# MC1.net
KiCad netlist of a schematic drawn in Altium Designer
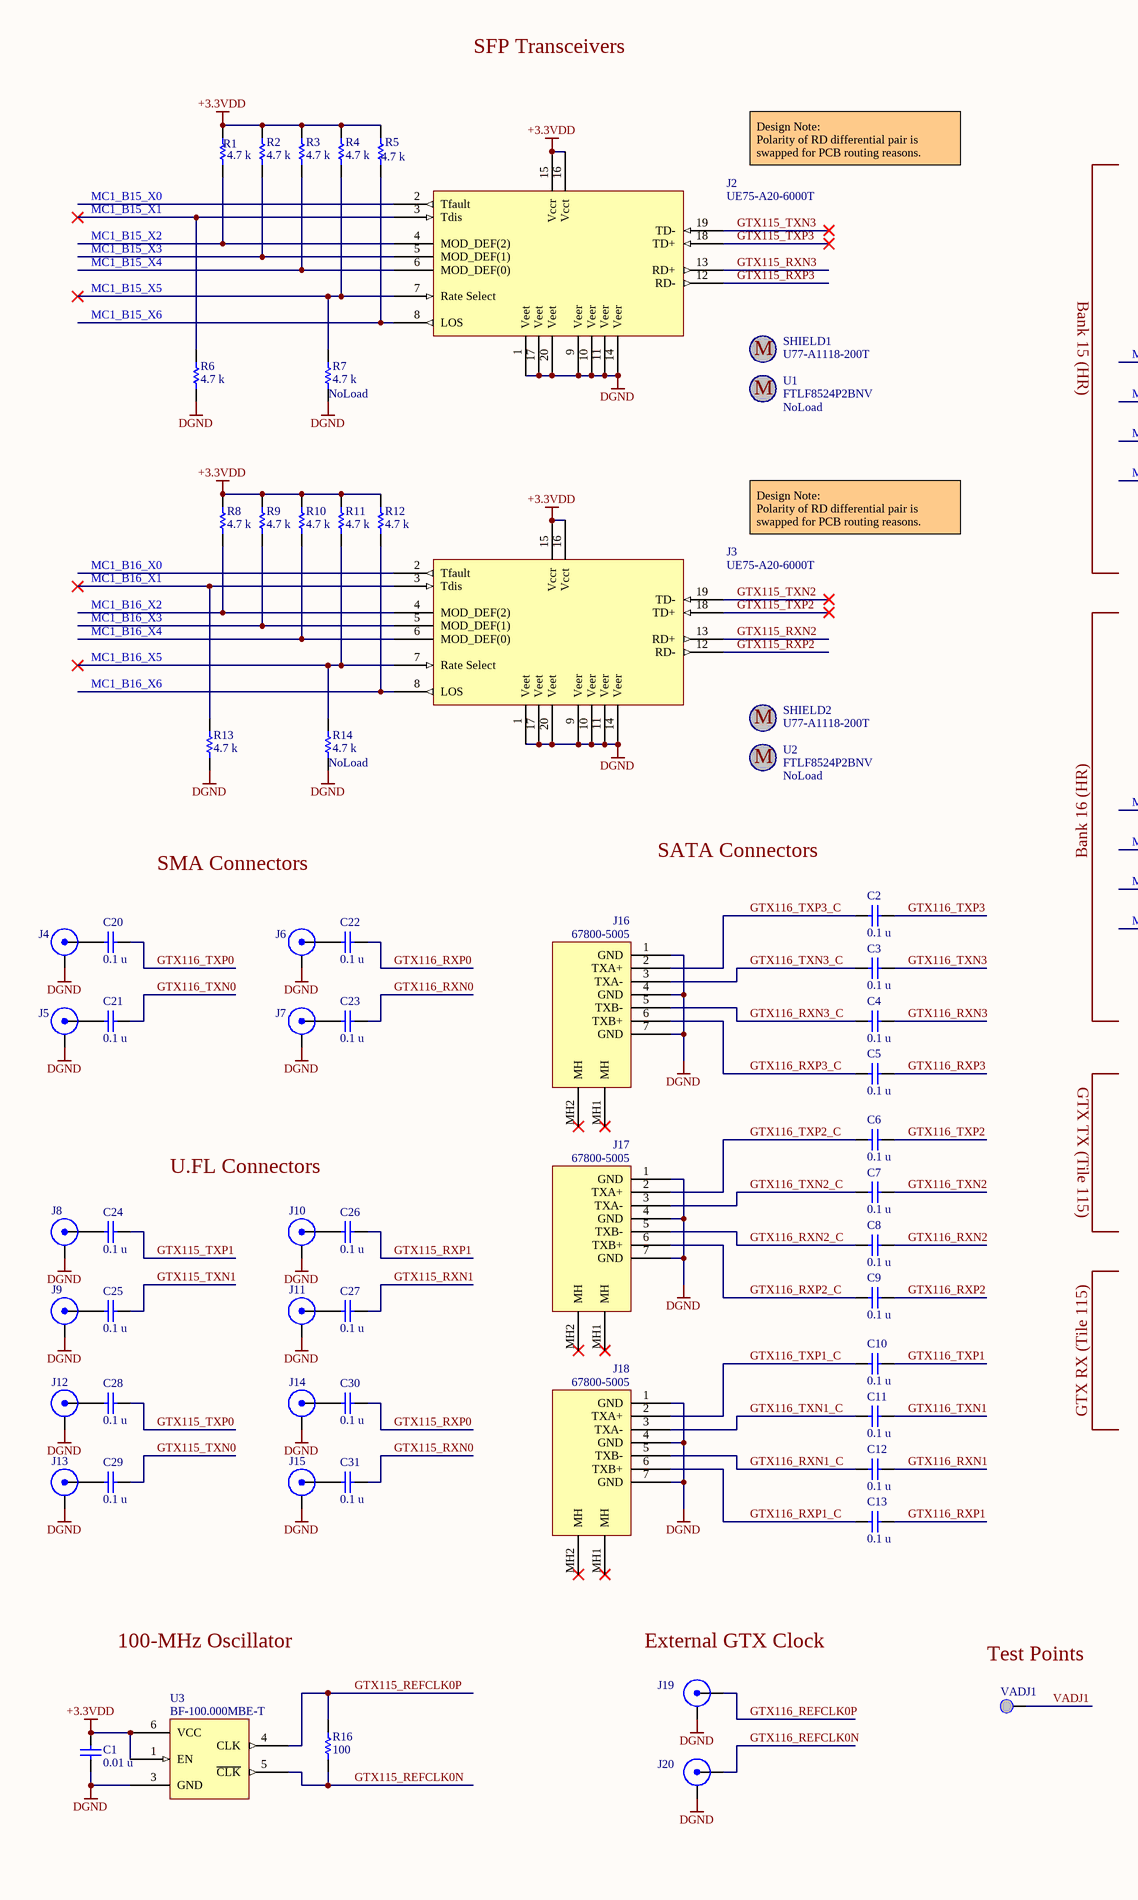
[diagram p0: MC1.SchDoc, left]
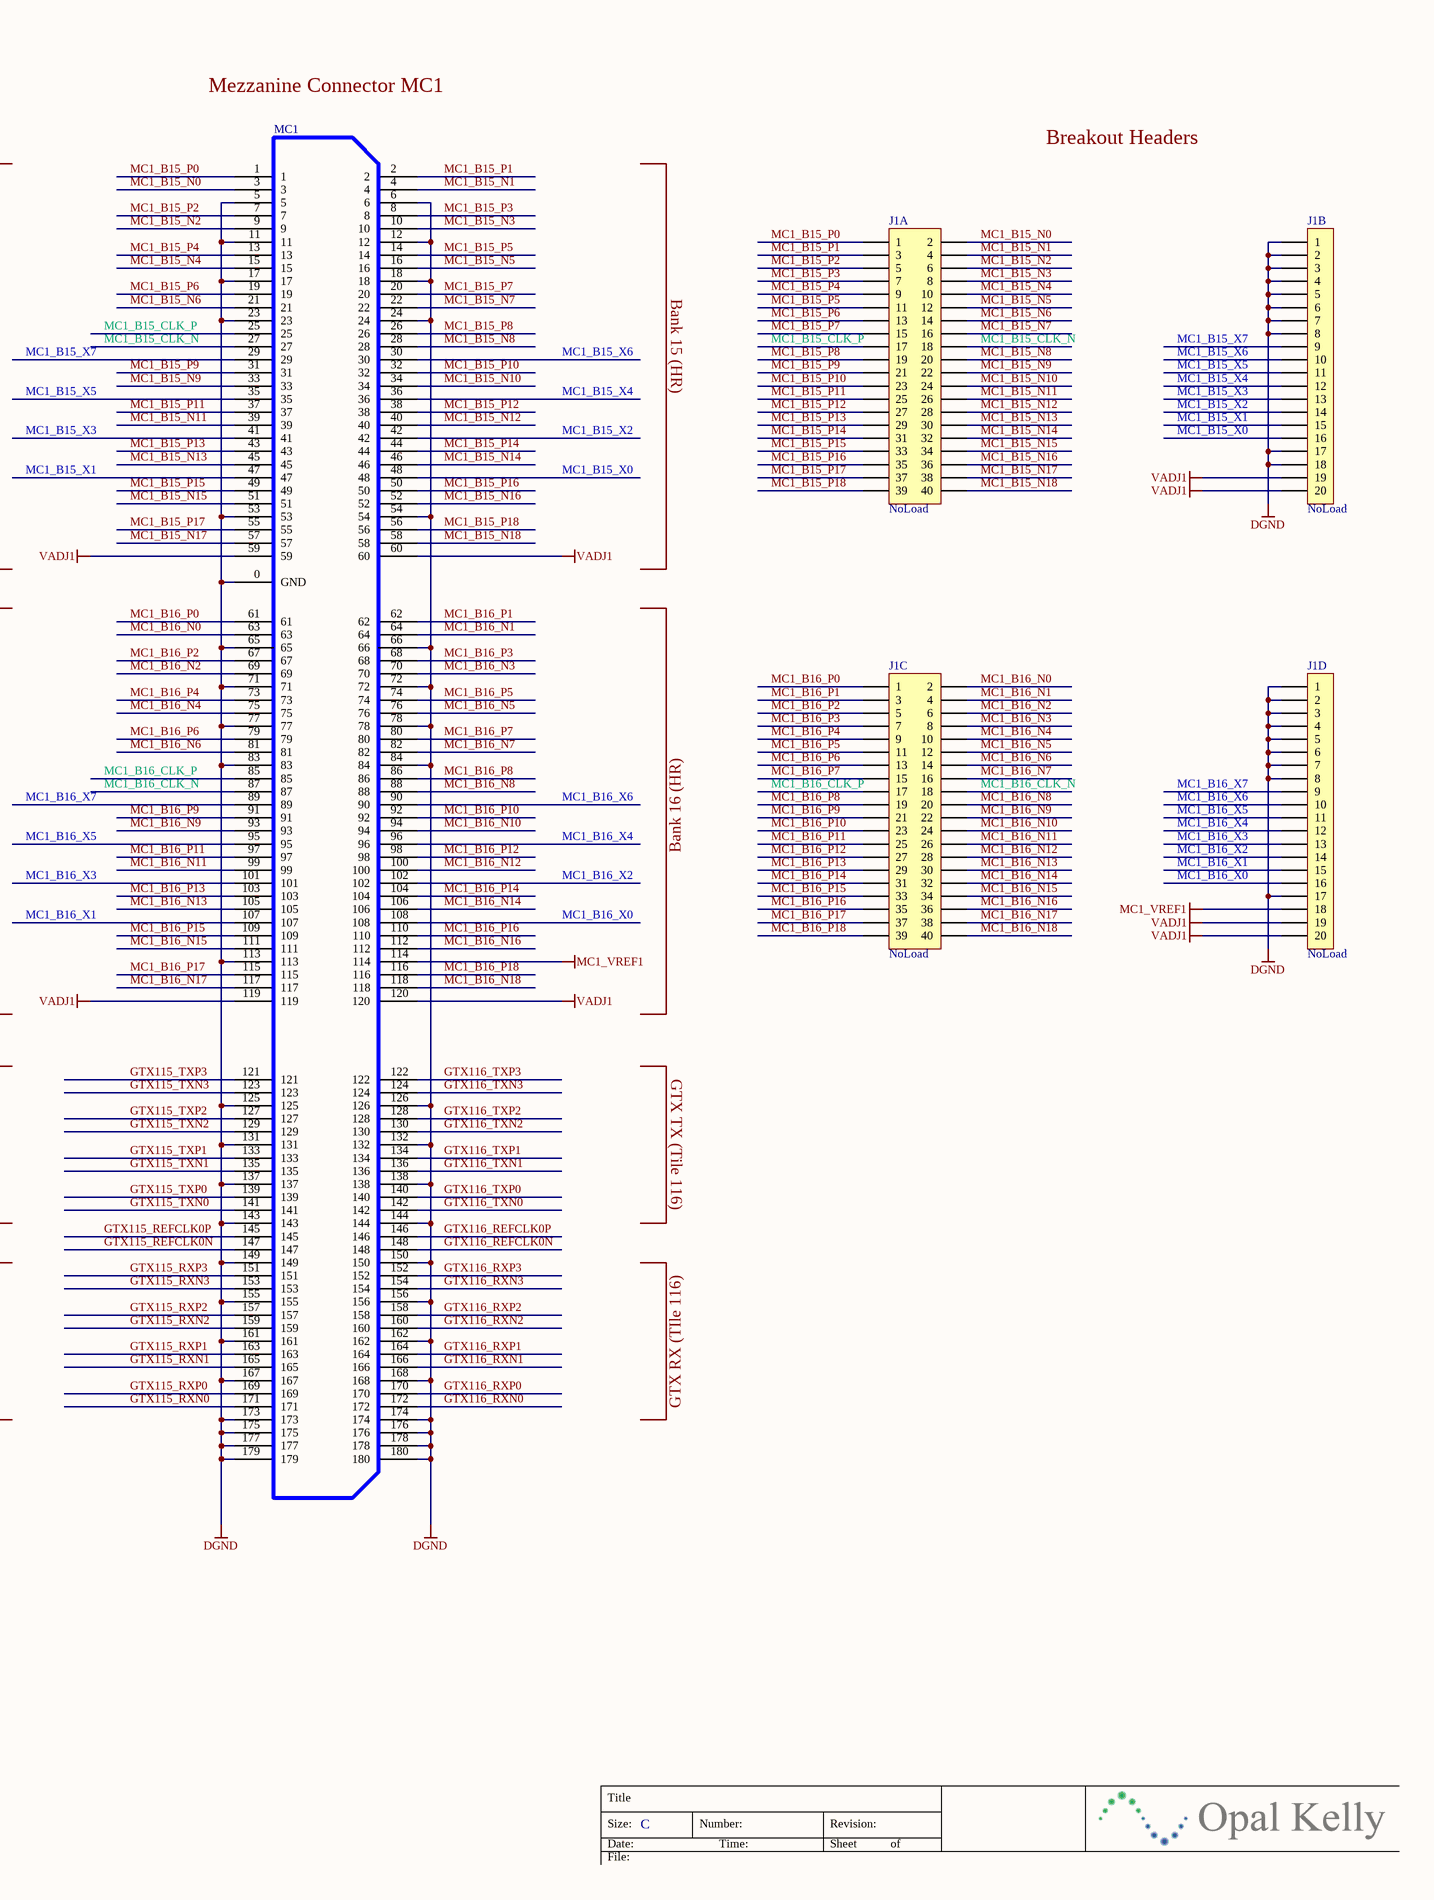
[diagram p1: MC1.SchDoc, right]

(export (version "E")
  (design (tool "Eeschema 10.0.6"))
  (components
    (comp (ref "C1")
      (value "0.01 u")
      (footprint "CAPC1005N")
      (description "Ceramic Capacitor")
      (fields (field (name "MANUFACTURER") "Kemet") (field (name "PARTNUMBER") "000295"))
      (libsource (lib "Aligni") (part "Capacitor"))
    )
    (comp (ref "C2")
      (value "0.1 u")
      (footprint "CAPC1005N")
      (description "Ceramic capacitor")
      (fields (field (name "MANUFACTURER") "Kemet") (field (name "PARTNUMBER") "000070"))
      (libsource (lib "Aligni") (part "Capacitor"))
    )
    (comp (ref "C3")
      (value "0.1 u")
      (footprint "CAPC1005N")
      (description "Ceramic capacitor")
      (fields (field (name "MANUFACTURER") "Kemet") (field (name "PARTNUMBER") "000070"))
      (libsource (lib "Aligni") (part "Capacitor"))
    )
    (comp (ref "C4")
      (value "0.1 u")
      (footprint "CAPC1005N")
      (description "Ceramic capacitor")
      (fields (field (name "MANUFACTURER") "Kemet") (field (name "PARTNUMBER") "000070"))
      (libsource (lib "Aligni") (part "Capacitor"))
    )
    (comp (ref "C5")
      (value "0.1 u")
      (footprint "CAPC1005N")
      (description "Ceramic capacitor")
      (fields (field (name "MANUFACTURER") "Kemet") (field (name "PARTNUMBER") "000070"))
      (libsource (lib "Aligni") (part "Capacitor"))
    )
    (comp (ref "C6")
      (value "0.1 u")
      (footprint "CAPC1005N")
      (description "Ceramic capacitor")
      (fields (field (name "MANUFACTURER") "Kemet") (field (name "PARTNUMBER") "000070"))
      (libsource (lib "Aligni") (part "Capacitor"))
    )
    (comp (ref "C7")
      (value "0.1 u")
      (footprint "CAPC1005N")
      (description "Ceramic capacitor")
      (fields (field (name "MANUFACTURER") "Kemet") (field (name "PARTNUMBER") "000070"))
      (libsource (lib "Aligni") (part "Capacitor"))
    )
    (comp (ref "C8")
      (value "0.1 u")
      (footprint "CAPC1005N")
      (description "Ceramic capacitor")
      (fields (field (name "MANUFACTURER") "Kemet") (field (name "PARTNUMBER") "000070"))
      (libsource (lib "Aligni") (part "Capacitor"))
    )
    (comp (ref "C9")
      (value "0.1 u")
      (footprint "CAPC1005N")
      (description "Ceramic capacitor")
      (fields (field (name "MANUFACTURER") "Kemet") (field (name "PARTNUMBER") "000070"))
      (libsource (lib "Aligni") (part "Capacitor"))
    )
    (comp (ref "C10")
      (value "0.1 u")
      (footprint "CAPC1005N")
      (description "Ceramic capacitor")
      (fields (field (name "MANUFACTURER") "Kemet") (field (name "PARTNUMBER") "000070"))
      (libsource (lib "Aligni") (part "Capacitor"))
    )
    (comp (ref "C11")
      (value "0.1 u")
      (footprint "CAPC1005N")
      (description "Ceramic capacitor")
      (fields (field (name "MANUFACTURER") "Kemet") (field (name "PARTNUMBER") "000070"))
      (libsource (lib "Aligni") (part "Capacitor"))
    )
    (comp (ref "C12")
      (value "0.1 u")
      (footprint "CAPC1005N")
      (description "Ceramic capacitor")
      (fields (field (name "MANUFACTURER") "Kemet") (field (name "PARTNUMBER") "000070"))
      (libsource (lib "Aligni") (part "Capacitor"))
    )
    (comp (ref "C13")
      (value "0.1 u")
      (footprint "CAPC1005N")
      (description "Ceramic capacitor")
      (fields (field (name "MANUFACTURER") "Kemet") (field (name "PARTNUMBER") "000070"))
      (libsource (lib "Aligni") (part "Capacitor"))
    )
    (comp (ref "C20")
      (value "0.1 u")
      (footprint "CAPC1005N")
      (description "Ceramic capacitor")
      (fields (field (name "MANUFACTURER") "Kemet") (field (name "PARTNUMBER") "000070"))
      (libsource (lib "Aligni") (part "Capacitor"))
    )
    (comp (ref "C21")
      (value "0.1 u")
      (footprint "CAPC1005N")
      (description "Ceramic capacitor")
      (fields (field (name "MANUFACTURER") "Kemet") (field (name "PARTNUMBER") "000070"))
      (libsource (lib "Aligni") (part "Capacitor"))
    )
    (comp (ref "C22")
      (value "0.1 u")
      (footprint "CAPC1005N")
      (description "Ceramic capacitor")
      (fields (field (name "MANUFACTURER") "Kemet") (field (name "PARTNUMBER") "000070"))
      (libsource (lib "Aligni") (part "Capacitor"))
    )
    (comp (ref "C23")
      (value "0.1 u")
      (footprint "CAPC1005N")
      (description "Ceramic capacitor")
      (fields (field (name "MANUFACTURER") "Kemet") (field (name "PARTNUMBER") "000070"))
      (libsource (lib "Aligni") (part "Capacitor"))
    )
    (comp (ref "C24")
      (value "0.1 u")
      (footprint "CAPC1005N")
      (description "Ceramic capacitor")
      (fields (field (name "MANUFACTURER") "Kemet") (field (name "PARTNUMBER") "000070"))
      (libsource (lib "Aligni") (part "Capacitor"))
    )
    (comp (ref "C25")
      (value "0.1 u")
      (footprint "CAPC1005N")
      (description "Ceramic capacitor")
      (fields (field (name "MANUFACTURER") "Kemet") (field (name "PARTNUMBER") "000070"))
      (libsource (lib "Aligni") (part "Capacitor"))
    )
    (comp (ref "C26")
      (value "0.1 u")
      (footprint "CAPC1005N")
      (description "Ceramic capacitor")
      (fields (field (name "MANUFACTURER") "Kemet") (field (name "PARTNUMBER") "000070"))
      (libsource (lib "Aligni") (part "Capacitor"))
    )
    (comp (ref "C27")
      (value "0.1 u")
      (footprint "CAPC1005N")
      (description "Ceramic capacitor")
      (fields (field (name "MANUFACTURER") "Kemet") (field (name "PARTNUMBER") "000070"))
      (libsource (lib "Aligni") (part "Capacitor"))
    )
    (comp (ref "C28")
      (value "0.1 u")
      (footprint "CAPC1005N")
      (description "Ceramic capacitor")
      (fields (field (name "MANUFACTURER") "Kemet") (field (name "PARTNUMBER") "000070"))
      (libsource (lib "Aligni") (part "Capacitor"))
    )
    (comp (ref "C29")
      (value "0.1 u")
      (footprint "CAPC1005N")
      (description "Ceramic capacitor")
      (fields (field (name "MANUFACTURER") "Kemet") (field (name "PARTNUMBER") "000070"))
      (libsource (lib "Aligni") (part "Capacitor"))
    )
    (comp (ref "C30")
      (value "0.1 u")
      (footprint "CAPC1005N")
      (description "Ceramic capacitor")
      (fields (field (name "MANUFACTURER") "Kemet") (field (name "PARTNUMBER") "000070"))
      (libsource (lib "Aligni") (part "Capacitor"))
    )
    (comp (ref "C31")
      (value "0.1 u")
      (footprint "CAPC1005N")
      (description "Ceramic capacitor")
      (fields (field (name "MANUFACTURER") "Kemet") (field (name "PARTNUMBER") "000070"))
      (libsource (lib "Aligni") (part "Capacitor"))
    )
    (comp (ref "J1A")
      (value "0877584016")
      (footprint "HDR2X20-2MM")
      (description "2mm header, 20x2, thru-hole")
      (fields
        (field (name "MANUFACTURER") "Molex")
        (field (name "PARTNUMBER") "000583")
        (field (name "NOLOAD") "NoLoad")
      )
      (libsource (lib "Aligni") (part "Header 20X2"))
    )
    (comp (ref "J1B")
      (value "Header, 20-Pin, Single Row")
      (footprint "HDR1X20-2MM")
      (description "2mm header, 20x1, thru-hole")
      (fields
        (field (name "PARTNUMBER") "001334")
        (field (name "MANUFACTURER") "3M")
        (field (name "NOLOAD") "NoLoad")
      )
      (libsource (lib "Aligni") (part "Header 1X20"))
    )
    (comp (ref "J1C")
      (value "0877584016")
      (footprint "HDR2X20-2MM")
      (description "2mm header, 20x2, thru-hole")
      (fields
        (field (name "MANUFACTURER") "Molex")
        (field (name "PARTNUMBER") "000583")
        (field (name "NOLOAD") "NoLoad")
      )
      (libsource (lib "Aligni") (part "Header 20X2"))
    )
    (comp (ref "J1D")
      (value "Header, 20-Pin, Single Row")
      (footprint "HDR1X20-2MM")
      (description "2mm header, 20x1, thru-hole")
      (fields
        (field (name "PARTNUMBER") "001334")
        (field (name "MANUFACTURER") "3M")
        (field (name "NOLOAD") "NoLoad")
      )
      (libsource (lib "Aligni") (part "Header 1X20"))
    )
    (comp (ref "J2")
      (value "UE75-A20-6000T")
      (footprint "SFP_RCPT_20_CAGE")
      (description "SFP 20-POS Recepticle")
      (fields (field (name "MANUFACTURER") "Amphenol") (field (name "PARTNUMBER") "000986"))
      (libsource (lib "Aligni") (part "SFP_RCPT"))
    )
    (comp (ref "J3")
      (value "UE75-A20-6000T")
      (footprint "SFP_RCPT_20_CAGE")
      (description "SFP 20-POS Recepticle")
      (fields (field (name "MANUFACTURER") "Amphenol") (field (name "PARTNUMBER") "000986"))
      (libsource (lib "Aligni") (part "SFP_RCPT"))
    )
    (comp (ref "J4")
      (value "TXP0")
      (footprint "SMA:SMA")
      (description "Straight SMA PCB Mount")
      (fields (field (name "MANUFACTURER") "Amphenol") (field (name "PARTNUMBER") "000974"))
      (libsource (lib "Aligni") (part "RF"))
    )
    (comp (ref "J5")
      (value "TXN0")
      (footprint "SMA:SMA")
      (description "Straight SMA PCB Mount")
      (fields (field (name "MANUFACTURER") "Amphenol") (field (name "PARTNUMBER") "000974"))
      (libsource (lib "Aligni") (part "RF"))
    )
    (comp (ref "J6")
      (value "RXP0")
      (footprint "SMA:SMA")
      (description "Straight SMA PCB Mount")
      (fields (field (name "MANUFACTURER") "Amphenol") (field (name "PARTNUMBER") "000974"))
      (libsource (lib "Aligni") (part "RF"))
    )
    (comp (ref "J7")
      (value "RXN0")
      (footprint "SMA:SMA")
      (description "Straight SMA PCB Mount")
      (fields (field (name "MANUFACTURER") "Amphenol") (field (name "PARTNUMBER") "000974"))
      (libsource (lib "Aligni") (part "RF"))
    )
    (comp (ref "J8")
      (value "TXP1")
      (footprint "UFL-R-SMT-1")
      (description "U.FL surface-mount coaxial connector")
      (fields (field (name "MANUFACTURER") "Hirose") (field (name "PARTNUMBER") "001335"))
      (libsource (lib "Aligni") (part "RF"))
    )
    (comp (ref "J9")
      (value "TXN1")
      (footprint "UFL-R-SMT-1")
      (description "U.FL surface-mount coaxial connector")
      (fields (field (name "MANUFACTURER") "Hirose") (field (name "PARTNUMBER") "001335"))
      (libsource (lib "Aligni") (part "RF"))
    )
    (comp (ref "J10")
      (value "RXP1")
      (footprint "UFL-R-SMT-1")
      (description "U.FL surface-mount coaxial connector")
      (fields (field (name "MANUFACTURER") "Hirose") (field (name "PARTNUMBER") "001335"))
      (libsource (lib "Aligni") (part "RF"))
    )
    (comp (ref "J11")
      (value "RXN1")
      (footprint "UFL-R-SMT-1")
      (description "U.FL surface-mount coaxial connector")
      (fields (field (name "MANUFACTURER") "Hirose") (field (name "PARTNUMBER") "001335"))
      (libsource (lib "Aligni") (part "RF"))
    )
    (comp (ref "J12")
      (value "TXP0")
      (footprint "UFL-R-SMT-1")
      (description "U.FL surface-mount coaxial connector")
      (fields (field (name "MANUFACTURER") "Hirose") (field (name "PARTNUMBER") "001335"))
      (libsource (lib "Aligni") (part "RF"))
    )
    (comp (ref "J13")
      (value "TXN0")
      (footprint "UFL-R-SMT-1")
      (description "U.FL surface-mount coaxial connector")
      (fields (field (name "MANUFACTURER") "Hirose") (field (name "PARTNUMBER") "001335"))
      (libsource (lib "Aligni") (part "RF"))
    )
    (comp (ref "J14")
      (value "RXP0")
      (footprint "UFL-R-SMT-1")
      (description "U.FL surface-mount coaxial connector")
      (fields (field (name "MANUFACTURER") "Hirose") (field (name "PARTNUMBER") "001335"))
      (libsource (lib "Aligni") (part "RF"))
    )
    (comp (ref "J15")
      (value "RXN0")
      (footprint "UFL-R-SMT-1")
      (description "U.FL surface-mount coaxial connector")
      (fields (field (name "MANUFACTURER") "Hirose") (field (name "PARTNUMBER") "001335"))
      (libsource (lib "Aligni") (part "RF"))
    )
    (comp (ref "J16")
      (value "67800-5005")
      (footprint "MOLEX-67800-5005")
      (description "SATA 7-pin receptacle")
      (fields (field (name "MANUFACTURER") "Molex") (field (name "PARTNUMBER") "000988"))
      (libsource (lib "Aligni") (part "SATA-Signal"))
    )
    (comp (ref "J17")
      (value "67800-5005")
      (footprint "MOLEX-67800-5005")
      (description "SATA 7-pin receptacle")
      (fields (field (name "MANUFACTURER") "Molex") (field (name "PARTNUMBER") "000988"))
      (libsource (lib "Aligni") (part "SATA-Signal"))
    )
    (comp (ref "J18")
      (value "67800-5005")
      (footprint "MOLEX-67800-5005")
      (description "SATA 7-pin receptacle")
      (fields (field (name "MANUFACTURER") "Molex") (field (name "PARTNUMBER") "000988"))
      (libsource (lib "Aligni") (part "SATA-Signal"))
    )
    (comp (ref "J19")
      (value "901-144-8RFX")
      (footprint "SMA")
      (description "Straight SMA PCB Mount")
      (fields (field (name "MANUFACTURER") "Amphenol") (field (name "PARTNUMBER") "000974"))
      (libsource (lib "Aligni") (part "RF"))
    )
    (comp (ref "J20")
      (value "901-144-8RFX")
      (footprint "SMA")
      (description "Straight SMA PCB Mount")
      (fields (field (name "MANUFACTURER") "Amphenol") (field (name "PARTNUMBER") "000974"))
      (libsource (lib "Aligni") (part "RF"))
    )
    (comp (ref "MC1")
      (value "QTH-090-01-F-D-A")
      (footprint "QTH-090-01-X-D")
      (description "0.5mm hi-speed, high-density header (Female)")
      (fields (field (name "MANUFACTURER") "Samtec") (field (name "PARTNUMBER") "000876"))
      (libsource (lib "Aligni") (part "QTH-090"))
    )
    (comp (ref "R1")
      (value "4.7 k")
      (footprint "RESC1005N")
      (description "Thick-film resistor")
      (fields (field (name "MANUFACTURER") "Vishay") (field (name "PARTNUMBER") "000754"))
      (libsource (lib "Aligni") (part "Resistor"))
    )
    (comp (ref "R2")
      (value "4.7 k")
      (footprint "RESC1005N")
      (description "Thick-film resistor")
      (fields (field (name "MANUFACTURER") "Vishay") (field (name "PARTNUMBER") "000754"))
      (libsource (lib "Aligni") (part "Resistor"))
    )
    (comp (ref "R3")
      (value "4.7 k")
      (footprint "RESC1005N")
      (description "Thick-film resistor")
      (fields (field (name "MANUFACTURER") "Vishay") (field (name "PARTNUMBER") "000754"))
      (libsource (lib "Aligni") (part "Resistor"))
    )
    (comp (ref "R4")
      (value "4.7 k")
      (footprint "RESC1005N")
      (description "Thick-film resistor")
      (fields (field (name "MANUFACTURER") "Vishay") (field (name "PARTNUMBER") "000754"))
      (libsource (lib "Aligni") (part "Resistor"))
    )
    (comp (ref "R5")
      (value "4.7 k")
      (footprint "RESC1005N")
      (description "Thick-film resistor")
      (fields (field (name "MANUFACTURER") "Vishay") (field (name "PARTNUMBER") "000754"))
      (libsource (lib "Aligni") (part "Resistor"))
    )
    (comp (ref "R6")
      (value "4.7 k")
      (footprint "RESC1005N")
      (description "Thick-film resistor")
      (fields (field (name "MANUFACTURER") "Vishay") (field (name "PARTNUMBER") "000754"))
      (libsource (lib "Aligni") (part "Resistor"))
    )
    (comp (ref "R7")
      (value "4.7 k")
      (footprint "RESC1005N")
      (description "Thick-film resistor")
      (fields
        (field (name "MANUFACTURER") "Vishay")
        (field (name "PARTNUMBER") "000754")
        (field (name "NOLOAD") "NoLoad")
      )
      (libsource (lib "Aligni") (part "Resistor"))
    )
    (comp (ref "R8")
      (value "4.7 k")
      (footprint "RESC1005N")
      (description "Thick-film resistor")
      (fields (field (name "MANUFACTURER") "Vishay") (field (name "PARTNUMBER") "000754"))
      (libsource (lib "Aligni") (part "Resistor"))
    )
    (comp (ref "R9")
      (value "4.7 k")
      (footprint "RESC1005N")
      (description "Thick-film resistor")
      (fields (field (name "MANUFACTURER") "Vishay") (field (name "PARTNUMBER") "000754"))
      (libsource (lib "Aligni") (part "Resistor"))
    )
    (comp (ref "R10")
      (value "4.7 k")
      (footprint "RESC1005N")
      (description "Thick-film resistor")
      (fields (field (name "MANUFACTURER") "Vishay") (field (name "PARTNUMBER") "000754"))
      (libsource (lib "Aligni") (part "Resistor"))
    )
    (comp (ref "R11")
      (value "4.7 k")
      (footprint "RESC1005N")
      (description "Thick-film resistor")
      (fields (field (name "MANUFACTURER") "Vishay") (field (name "PARTNUMBER") "000754"))
      (libsource (lib "Aligni") (part "Resistor"))
    )
    (comp (ref "R12")
      (value "4.7 k")
      (footprint "RESC1005N")
      (description "Thick-film resistor")
      (fields (field (name "MANUFACTURER") "Vishay") (field (name "PARTNUMBER") "000754"))
      (libsource (lib "Aligni") (part "Resistor"))
    )
    (comp (ref "R13")
      (value "4.7 k")
      (footprint "RESC1005N")
      (description "Thick-film resistor")
      (fields (field (name "MANUFACTURER") "Vishay") (field (name "PARTNUMBER") "000754"))
      (libsource (lib "Aligni") (part "Resistor"))
    )
    (comp (ref "R14")
      (value "4.7 k")
      (footprint "RESC1005N")
      (description "Thick-film resistor")
      (fields
        (field (name "MANUFACTURER") "Vishay")
        (field (name "PARTNUMBER") "000754")
        (field (name "NOLOAD") "NoLoad")
      )
      (libsource (lib "Aligni") (part "Resistor"))
    )
    (comp (ref "R16")
      (value "100")
      (footprint "RESC1608N")
      (description "Thick-film resistor")
      (fields (field (name "MANUFACTURER") "Vishay") (field (name "PARTNUMBER") "000789"))
      (libsource (lib "Aligni") (part "Resistor"))
    )
    (comp (ref "SHIELD1")
      (value "U77-A1118-200T")
      (description "SFP Single Cage")
      (fields (field (name "MANUFACTURER") "Amphenol") (field (name "PARTNUMBER") "000987"))
      (libsource (lib "Aligni") (part "MECHANICAL"))
    )
    (comp (ref "SHIELD2")
      (value "U77-A1118-200T")
      (description "SFP Single Cage")
      (fields (field (name "MANUFACTURER") "Amphenol") (field (name "PARTNUMBER") "000987"))
      (libsource (lib "Aligni") (part "MECHANICAL"))
    )
    (comp (ref "TP1")
      (value "VADJ1")
      (footprint "TP_MED")
      (description "Testpoint")
      (fields (field (name "MANUFACTURER") "Keystone Electronics") (field (name "PARTNUMBER") "000265"))
      (libsource (lib "Aligni") (part "TESTPOINT"))
    )
    (comp (ref "U1")
      (value "FTLF8524P2BNV")
      (description "SFP Transceiver")
      (fields
        (field (name "MANUFACTURER") "Finisar")
        (field (name "PARTNUMBER") "000985")
        (field (name "NOLOAD") "NoLoad")
      )
      (libsource (lib "Aligni-CHI") (part "MECHANICAL"))
    )
    (comp (ref "U2")
      (value "FTLF8524P2BNV")
      (description "SFP Transceiver")
      (fields
        (field (name "MANUFACTURER") "Finisar")
        (field (name "PARTNUMBER") "000985")
        (field (name "NOLOAD") "NoLoad")
      )
      (libsource (lib "Aligni-CHI") (part "MECHANICAL"))
    )
    (comp (ref "U3")
      (value "BF-100.000MBE-T")
      (footprint "OSC_SMD6_5x7")
      (description "100 MHz LVDS oscillator")
      (fields (field (name "MANUFACTURER") "TXC Corporation") (field (name "PARTNUMBER") "000846"))
      (libsource (lib "Aligni") (part "OSC_CCPD"))
    )
  )
  (nets
    (net (code "1") (name "+3.3VDD") (class "Default")
      (node (ref "C1") (pin "2") (pinfunction "2_2") (pintype "passive"))
      (node (ref "J2") (pin "15") (pinfunction "Vccr_15") (pintype "power_in"))
      (node (ref "J2") (pin "16") (pinfunction "Vcct_16") (pintype "power_in"))
      (node (ref "J3") (pin "15") (pinfunction "Vccr_15") (pintype "power_in"))
      (node (ref "J3") (pin "16") (pinfunction "Vcct_16") (pintype "power_in"))
      (node (ref "R1") (pin "2") (pinfunction "2_2") (pintype "passive"))
      (node (ref "R10") (pin "1") (pinfunction "1_1") (pintype "passive"))
      (node (ref "R11") (pin "1") (pinfunction "1_1") (pintype "passive"))
      (node (ref "R12") (pin "1") (pinfunction "1_1") (pintype "passive"))
      (node (ref "R2") (pin "2") (pinfunction "2_2") (pintype "passive"))
      (node (ref "R3") (pin "2") (pinfunction "2_2") (pintype "passive"))
      (node (ref "R4") (pin "2") (pinfunction "2_2") (pintype "passive"))
      (node (ref "R5") (pin "2") (pinfunction "2_2") (pintype "passive"))
      (node (ref "R8") (pin "1") (pinfunction "1_1") (pintype "passive"))
      (node (ref "R9") (pin "1") (pinfunction "1_1") (pintype "passive"))
      (node (ref "U3") (pin "1") (pinfunction "EN_1") (pintype "input"))
      (node (ref "U3") (pin "6") (pinfunction "VCC_6") (pintype "power_in"))
    )
    (net (code "2") (name "/GTX115_REFCLK0N") (class "Default")
      (node (ref "MC1") (pin "147") (pinfunction "147_147") (pintype "passive"))
      (node (ref "R16") (pin "1") (pinfunction "1_1") (pintype "passive"))
      (node (ref "U3") (pin "5") (pinfunction "~{CLK}_5") (pintype "output"))
    )
    (net (code "3") (name "/GTX115_REFCLK0P") (class "Default")
      (node (ref "MC1") (pin "145") (pinfunction "145_145") (pintype "passive"))
      (node (ref "R16") (pin "2") (pinfunction "2_2") (pintype "passive"))
      (node (ref "U3") (pin "4") (pinfunction "CLK_4") (pintype "output"))
    )
    (net (code "4") (name "/GTX115_RXN0") (class "Default")
      (node (ref "C31") (pin "2") (pinfunction "2_2") (pintype "passive"))
      (node (ref "MC1") (pin "171") (pinfunction "171_171") (pintype "passive"))
    )
    (net (code "5") (name "/GTX115_RXN1") (class "Default")
      (node (ref "C27") (pin "2") (pinfunction "2_2") (pintype "passive"))
      (node (ref "MC1") (pin "165") (pinfunction "165_165") (pintype "passive"))
    )
    (net (code "6") (name "/GTX115_RXN2") (class "Default")
      (node (ref "J3") (pin "13") (pinfunction "RD+_13") (pintype "output"))
      (node (ref "MC1") (pin "159") (pinfunction "159_159") (pintype "passive"))
    )
    (net (code "7") (name "/GTX115_RXN3") (class "Default")
      (node (ref "J2") (pin "13") (pinfunction "RD+_13") (pintype "output"))
      (node (ref "MC1") (pin "153") (pinfunction "153_153") (pintype "passive"))
    )
    (net (code "8") (name "/GTX115_RXP0") (class "Default")
      (node (ref "C30") (pin "2") (pinfunction "2_2") (pintype "passive"))
      (node (ref "MC1") (pin "169") (pinfunction "169_169") (pintype "passive"))
    )
    (net (code "9") (name "/GTX115_RXP1") (class "Default")
      (node (ref "C26") (pin "2") (pinfunction "2_2") (pintype "passive"))
      (node (ref "MC1") (pin "163") (pinfunction "163_163") (pintype "passive"))
    )
    (net (code "10") (name "/GTX115_RXP2") (class "Default")
      (node (ref "J3") (pin "12") (pinfunction "RD-_12") (pintype "output"))
      (node (ref "MC1") (pin "157") (pinfunction "157_157") (pintype "passive"))
    )
    (net (code "11") (name "/GTX115_RXP3") (class "Default")
      (node (ref "J2") (pin "12") (pinfunction "RD-_12") (pintype "output"))
      (node (ref "MC1") (pin "151") (pinfunction "151_151") (pintype "passive"))
    )
    (net (code "12") (name "/GTX115_TXN0") (class "Default")
      (node (ref "C29") (pin "2") (pinfunction "2_2") (pintype "passive"))
      (node (ref "MC1") (pin "141") (pinfunction "141_141") (pintype "passive"))
    )
    (net (code "13") (name "/GTX115_TXN1") (class "Default")
      (node (ref "C25") (pin "2") (pinfunction "2_2") (pintype "passive"))
      (node (ref "MC1") (pin "135") (pinfunction "135_135") (pintype "passive"))
    )
    (net (code "14") (name "/GTX115_TXN2") (class "Default")
      (node (ref "J3") (pin "19") (pinfunction "TD-_19") (pintype "input"))
      (node (ref "MC1") (pin "129") (pinfunction "129_129") (pintype "passive"))
    )
    (net (code "15") (name "/GTX115_TXN3") (class "Default")
      (node (ref "J2") (pin "19") (pinfunction "TD-_19") (pintype "input"))
      (node (ref "MC1") (pin "123") (pinfunction "123_123") (pintype "passive"))
    )
    (net (code "16") (name "/GTX115_TXP0") (class "Default")
      (node (ref "C28") (pin "2") (pinfunction "2_2") (pintype "passive"))
      (node (ref "MC1") (pin "139") (pinfunction "139_139") (pintype "passive"))
    )
    (net (code "17") (name "/GTX115_TXP1") (class "Default")
      (node (ref "C24") (pin "2") (pinfunction "2_2") (pintype "passive"))
      (node (ref "MC1") (pin "133") (pinfunction "133_133") (pintype "passive"))
    )
    (net (code "18") (name "/GTX115_TXP2") (class "Default")
      (node (ref "J3") (pin "18") (pinfunction "TD+_18") (pintype "input"))
      (node (ref "MC1") (pin "127") (pinfunction "127_127") (pintype "passive"))
    )
    (net (code "19") (name "/GTX115_TXP3") (class "Default")
      (node (ref "J2") (pin "18") (pinfunction "TD+_18") (pintype "input"))
      (node (ref "MC1") (pin "121") (pinfunction "121_121") (pintype "passive"))
    )
    (net (code "20") (name "/GTX116_REFCLK0N") (class "Default")
      (node (ref "J20") (pin "1") (pinfunction "SIGNAL_1") (pintype "passive"))
      (node (ref "MC1") (pin "148") (pinfunction "148_148") (pintype "passive"))
    )
    (net (code "21") (name "/GTX116_REFCLK0P") (class "Default")
      (node (ref "J19") (pin "1") (pinfunction "SIGNAL_1") (pintype "passive"))
      (node (ref "MC1") (pin "146") (pinfunction "146_146") (pintype "passive"))
    )
    (net (code "22") (name "/GTX116_RXN0") (class "Default")
      (node (ref "C23") (pin "2") (pinfunction "2_2") (pintype "passive"))
      (node (ref "MC1") (pin "172") (pinfunction "172_172") (pintype "passive"))
    )
    (net (code "23") (name "/GTX116_RXN1") (class "Default")
      (node (ref "C12") (pin "2") (pinfunction "2_2") (pintype "passive"))
      (node (ref "MC1") (pin "166") (pinfunction "166_166") (pintype "passive"))
    )
    (net (code "24") (name "/GTX116_RXN1_C") (class "Default")
      (node (ref "C12") (pin "1") (pinfunction "1_1") (pintype "passive"))
      (node (ref "J18") (pin "5") (pinfunction "TXB-_5") (pintype "passive"))
    )
    (net (code "25") (name "/GTX116_RXN2") (class "Default")
      (node (ref "C8") (pin "2") (pinfunction "2_2") (pintype "passive"))
      (node (ref "MC1") (pin "160") (pinfunction "160_160") (pintype "passive"))
    )
    (net (code "26") (name "/GTX116_RXN2_C") (class "Default")
      (node (ref "C8") (pin "1") (pinfunction "1_1") (pintype "passive"))
      (node (ref "J17") (pin "5") (pinfunction "TXB-_5") (pintype "passive"))
    )
    (net (code "27") (name "/GTX116_RXN3") (class "Default")
      (node (ref "C4") (pin "2") (pinfunction "2_2") (pintype "passive"))
      (node (ref "MC1") (pin "154") (pinfunction "154_154") (pintype "passive"))
    )
    (net (code "28") (name "/GTX116_RXN3_C") (class "Default")
      (node (ref "C4") (pin "1") (pinfunction "1_1") (pintype "passive"))
      (node (ref "J16") (pin "5") (pinfunction "TXB-_5") (pintype "passive"))
    )
    (net (code "29") (name "/GTX116_RXP0") (class "Default")
      (node (ref "C22") (pin "2") (pinfunction "2_2") (pintype "passive"))
      (node (ref "MC1") (pin "170") (pinfunction "170_170") (pintype "passive"))
    )
    (net (code "30") (name "/GTX116_RXP1") (class "Default")
      (node (ref "C13") (pin "2") (pinfunction "2_2") (pintype "passive"))
      (node (ref "MC1") (pin "164") (pinfunction "164_164") (pintype "passive"))
    )
    (net (code "31") (name "/GTX116_RXP1_C") (class "Default")
      (node (ref "C13") (pin "1") (pinfunction "1_1") (pintype "passive"))
      (node (ref "J18") (pin "6") (pinfunction "TXB+_6") (pintype "passive"))
    )
    (net (code "32") (name "/GTX116_RXP2") (class "Default")
      (node (ref "C9") (pin "2") (pinfunction "2_2") (pintype "passive"))
      (node (ref "MC1") (pin "158") (pinfunction "158_158") (pintype "passive"))
    )
    (net (code "33") (name "/GTX116_RXP2_C") (class "Default")
      (node (ref "C9") (pin "1") (pinfunction "1_1") (pintype "passive"))
      (node (ref "J17") (pin "6") (pinfunction "TXB+_6") (pintype "passive"))
    )
    (net (code "34") (name "/GTX116_RXP3") (class "Default")
      (node (ref "C5") (pin "2") (pinfunction "2_2") (pintype "passive"))
      (node (ref "MC1") (pin "152") (pinfunction "152_152") (pintype "passive"))
    )
    (net (code "35") (name "/GTX116_RXP3_C") (class "Default")
      (node (ref "C5") (pin "1") (pinfunction "1_1") (pintype "passive"))
      (node (ref "J16") (pin "6") (pinfunction "TXB+_6") (pintype "passive"))
    )
    (net (code "36") (name "/GTX116_TXN0") (class "Default")
      (node (ref "C21") (pin "2") (pinfunction "2_2") (pintype "passive"))
      (node (ref "MC1") (pin "142") (pinfunction "142_142") (pintype "passive"))
    )
    (net (code "37") (name "/GTX116_TXN1") (class "Default")
      (node (ref "C11") (pin "2") (pinfunction "2_2") (pintype "passive"))
      (node (ref "MC1") (pin "136") (pinfunction "136_136") (pintype "passive"))
    )
    (net (code "38") (name "/GTX116_TXN1_C") (class "Default")
      (node (ref "C11") (pin "1") (pinfunction "1_1") (pintype "passive"))
      (node (ref "J18") (pin "3") (pinfunction "TXA-_3") (pintype "passive"))
    )
    (net (code "39") (name "/GTX116_TXN2") (class "Default")
      (node (ref "C7") (pin "2") (pinfunction "2_2") (pintype "passive"))
      (node (ref "MC1") (pin "130") (pinfunction "130_130") (pintype "passive"))
    )
    (net (code "40") (name "/GTX116_TXN2_C") (class "Default")
      (node (ref "C7") (pin "1") (pinfunction "1_1") (pintype "passive"))
      (node (ref "J17") (pin "3") (pinfunction "TXA-_3") (pintype "passive"))
    )
    (net (code "41") (name "/GTX116_TXN3") (class "Default")
      (node (ref "C3") (pin "2") (pinfunction "2_2") (pintype "passive"))
      (node (ref "MC1") (pin "124") (pinfunction "124_124") (pintype "passive"))
    )
    (net (code "42") (name "/GTX116_TXN3_C") (class "Default")
      (node (ref "C3") (pin "1") (pinfunction "1_1") (pintype "passive"))
      (node (ref "J16") (pin "3") (pinfunction "TXA-_3") (pintype "passive"))
    )
    (net (code "43") (name "/GTX116_TXP0") (class "Default")
      (node (ref "C20") (pin "2") (pinfunction "2_2") (pintype "passive"))
      (node (ref "MC1") (pin "140") (pinfunction "140_140") (pintype "passive"))
    )
    (net (code "44") (name "/GTX116_TXP1") (class "Default")
      (node (ref "C10") (pin "2") (pinfunction "2_2") (pintype "passive"))
      (node (ref "MC1") (pin "134") (pinfunction "134_134") (pintype "passive"))
    )
    (net (code "45") (name "/GTX116_TXP1_C") (class "Default")
      (node (ref "C10") (pin "1") (pinfunction "1_1") (pintype "passive"))
      (node (ref "J18") (pin "2") (pinfunction "TXA+_2") (pintype "passive"))
    )
    (net (code "46") (name "/GTX116_TXP2") (class "Default")
      (node (ref "C6") (pin "2") (pinfunction "2_2") (pintype "passive"))
      (node (ref "MC1") (pin "128") (pinfunction "128_128") (pintype "passive"))
    )
    (net (code "47") (name "/GTX116_TXP2_C") (class "Default")
      (node (ref "C6") (pin "1") (pinfunction "1_1") (pintype "passive"))
      (node (ref "J17") (pin "2") (pinfunction "TXA+_2") (pintype "passive"))
    )
    (net (code "48") (name "/GTX116_TXP3") (class "Default")
      (node (ref "C2") (pin "2") (pinfunction "2_2") (pintype "passive"))
      (node (ref "MC1") (pin "122") (pinfunction "122_122") (pintype "passive"))
    )
    (net (code "49") (name "/GTX116_TXP3_C") (class "Default")
      (node (ref "C2") (pin "1") (pinfunction "1_1") (pintype "passive"))
      (node (ref "J16") (pin "2") (pinfunction "TXA+_2") (pintype "passive"))
    )
    (net (code "50") (name "/MC1_B15_CLK_N") (class "Default")
      (node (ref "J1A") (pin "18") (pinfunction "18_18") (pintype "passive"))
      (node (ref "MC1") (pin "27") (pinfunction "27_27") (pintype "passive"))
    )
    (net (code "51") (name "/MC1_B15_CLK_P") (class "Default")
      (node (ref "J1A") (pin "17") (pinfunction "17_17") (pintype "passive"))
      (node (ref "MC1") (pin "25") (pinfunction "25_25") (pintype "passive"))
    )
    (net (code "52") (name "/MC1_B15_N0") (class "Default")
      (node (ref "J1A") (pin "2") (pinfunction "2_2") (pintype "passive"))
      (node (ref "MC1") (pin "3") (pinfunction "3_3") (pintype "passive"))
    )
    (net (code "53") (name "/MC1_B15_N1") (class "Default")
      (node (ref "J1A") (pin "4") (pinfunction "4_4") (pintype "passive"))
      (node (ref "MC1") (pin "4") (pinfunction "4_4") (pintype "passive"))
    )
    (net (code "54") (name "/MC1_B15_N2") (class "Default")
      (node (ref "J1A") (pin "6") (pinfunction "6_6") (pintype "passive"))
      (node (ref "MC1") (pin "9") (pinfunction "9_9") (pintype "passive"))
    )
    (net (code "55") (name "/MC1_B15_N3") (class "Default")
      (node (ref "J1A") (pin "8") (pinfunction "8_8") (pintype "passive"))
      (node (ref "MC1") (pin "10") (pinfunction "10_10") (pintype "passive"))
    )
    (net (code "56") (name "/MC1_B15_N4") (class "Default")
      (node (ref "J1A") (pin "10") (pinfunction "10_10") (pintype "passive"))
      (node (ref "MC1") (pin "15") (pinfunction "15_15") (pintype "passive"))
    )
    (net (code "57") (name "/MC1_B15_N5") (class "Default")
      (node (ref "J1A") (pin "12") (pinfunction "12_12") (pintype "passive"))
      (node (ref "MC1") (pin "16") (pinfunction "16_16") (pintype "passive"))
    )
    (net (code "58") (name "/MC1_B15_N6") (class "Default")
      (node (ref "J1A") (pin "14") (pinfunction "14_14") (pintype "passive"))
      (node (ref "MC1") (pin "21") (pinfunction "21_21") (pintype "passive"))
    )
    (net (code "59") (name "/MC1_B15_N7") (class "Default")
      (node (ref "J1A") (pin "16") (pinfunction "16_16") (pintype "passive"))
      (node (ref "MC1") (pin "22") (pinfunction "22_22") (pintype "passive"))
    )
    (net (code "60") (name "/MC1_B15_N8") (class "Default")
      (node (ref "J1A") (pin "20") (pinfunction "20_20") (pintype "passive"))
      (node (ref "MC1") (pin "28") (pinfunction "28_28") (pintype "passive"))
    )
    (net (code "61") (name "/MC1_B15_N9") (class "Default")
      (node (ref "J1A") (pin "22") (pinfunction "22_22") (pintype "passive"))
      (node (ref "MC1") (pin "33") (pinfunction "33_33") (pintype "passive"))
    )
    (net (code "62") (name "/MC1_B15_N10") (class "Default")
      (node (ref "J1A") (pin "24") (pinfunction "24_24") (pintype "passive"))
      (node (ref "MC1") (pin "34") (pinfunction "34_34") (pintype "passive"))
    )
    (net (code "63") (name "/MC1_B15_N11") (class "Default")
      (node (ref "J1A") (pin "26") (pinfunction "26_26") (pintype "passive"))
      (node (ref "MC1") (pin "39") (pinfunction "39_39") (pintype "passive"))
    )
    (net (code "64") (name "/MC1_B15_N12") (class "Default")
      (node (ref "J1A") (pin "28") (pinfunction "28_28") (pintype "passive"))
      (node (ref "MC1") (pin "40") (pinfunction "40_40") (pintype "passive"))
    )
    (net (code "65") (name "/MC1_B15_N13") (class "Default")
      (node (ref "J1A") (pin "30") (pinfunction "30_30") (pintype "passive"))
      (node (ref "MC1") (pin "45") (pinfunction "45_45") (pintype "passive"))
    )
    (net (code "66") (name "/MC1_B15_N14") (class "Default")
      (node (ref "J1A") (pin "32") (pinfunction "32_32") (pintype "passive"))
      (node (ref "MC1") (pin "46") (pinfunction "46_46") (pintype "passive"))
    )
    (net (code "67") (name "/MC1_B15_N15") (class "Default")
      (node (ref "J1A") (pin "34") (pinfunction "34_34") (pintype "passive"))
      (node (ref "MC1") (pin "51") (pinfunction "51_51") (pintype "passive"))
    )
    (net (code "68") (name "/MC1_B15_N16") (class "Default")
      (node (ref "J1A") (pin "36") (pinfunction "36_36") (pintype "passive"))
      (node (ref "MC1") (pin "52") (pinfunction "52_52") (pintype "passive"))
    )
    (net (code "69") (name "/MC1_B15_N17") (class "Default")
      (node (ref "J1A") (pin "38") (pinfunction "38_38") (pintype "passive"))
      (node (ref "MC1") (pin "57") (pinfunction "57_57") (pintype "passive"))
    )
    (net (code "70") (name "/MC1_B15_N18") (class "Default")
      (node (ref "J1A") (pin "40") (pinfunction "40_40") (pintype "passive"))
      (node (ref "MC1") (pin "58") (pinfunction "58_58") (pintype "passive"))
    )
    (net (code "71") (name "/MC1_B15_P0") (class "Default")
      (node (ref "J1A") (pin "1") (pinfunction "1_1") (pintype "passive"))
      (node (ref "MC1") (pin "1") (pinfunction "1_1") (pintype "passive"))
    )
    (net (code "72") (name "/MC1_B15_P1") (class "Default")
      (node (ref "J1A") (pin "3") (pinfunction "3_3") (pintype "passive"))
      (node (ref "MC1") (pin "2") (pinfunction "2_2") (pintype "passive"))
    )
    (net (code "73") (name "/MC1_B15_P2") (class "Default")
      (node (ref "J1A") (pin "5") (pinfunction "5_5") (pintype "passive"))
      (node (ref "MC1") (pin "7") (pinfunction "7_7") (pintype "passive"))
    )
    (net (code "74") (name "/MC1_B15_P3") (class "Default")
      (node (ref "J1A") (pin "7") (pinfunction "7_7") (pintype "passive"))
      (node (ref "MC1") (pin "8") (pinfunction "8_8") (pintype "passive"))
    )
    (net (code "75") (name "/MC1_B15_P4") (class "Default")
      (node (ref "J1A") (pin "9") (pinfunction "9_9") (pintype "passive"))
      (node (ref "MC1") (pin "13") (pinfunction "13_13") (pintype "passive"))
    )
    (net (code "76") (name "/MC1_B15_P5") (class "Default")
      (node (ref "J1A") (pin "11") (pinfunction "11_11") (pintype "passive"))
      (node (ref "MC1") (pin "14") (pinfunction "14_14") (pintype "passive"))
    )
    (net (code "77") (name "/MC1_B15_P6") (class "Default")
      (node (ref "J1A") (pin "13") (pinfunction "13_13") (pintype "passive"))
      (node (ref "MC1") (pin "19") (pinfunction "19_19") (pintype "passive"))
    )
    (net (code "78") (name "/MC1_B15_P7") (class "Default")
      (node (ref "J1A") (pin "15") (pinfunction "15_15") (pintype "passive"))
      (node (ref "MC1") (pin "20") (pinfunction "20_20") (pintype "passive"))
    )
    (net (code "79") (name "/MC1_B15_P8") (class "Default")
      (node (ref "J1A") (pin "19") (pinfunction "19_19") (pintype "passive"))
      (node (ref "MC1") (pin "26") (pinfunction "26_26") (pintype "passive"))
    )
    (net (code "80") (name "/MC1_B15_P9") (class "Default")
      (node (ref "J1A") (pin "21") (pinfunction "21_21") (pintype "passive"))
      (node (ref "MC1") (pin "31") (pinfunction "31_31") (pintype "passive"))
    )
    (net (code "81") (name "/MC1_B15_P10") (class "Default")
      (node (ref "J1A") (pin "23") (pinfunction "23_23") (pintype "passive"))
      (node (ref "MC1") (pin "32") (pinfunction "32_32") (pintype "passive"))
    )
    (net (code "82") (name "/MC1_B15_P11") (class "Default")
      (node (ref "J1A") (pin "25") (pinfunction "25_25") (pintype "passive"))
      (node (ref "MC1") (pin "37") (pinfunction "37_37") (pintype "passive"))
    )
    (net (code "83") (name "/MC1_B15_P12") (class "Default")
      (node (ref "J1A") (pin "27") (pinfunction "27_27") (pintype "passive"))
      (node (ref "MC1") (pin "38") (pinfunction "38_38") (pintype "passive"))
    )
    (net (code "84") (name "/MC1_B15_P13") (class "Default")
      (node (ref "J1A") (pin "29") (pinfunction "29_29") (pintype "passive"))
      (node (ref "MC1") (pin "43") (pinfunction "43_43") (pintype "passive"))
    )
    (net (code "85") (name "/MC1_B15_P14") (class "Default")
      (node (ref "J1A") (pin "31") (pinfunction "31_31") (pintype "passive"))
      (node (ref "MC1") (pin "44") (pinfunction "44_44") (pintype "passive"))
    )
    (net (code "86") (name "/MC1_B15_P15") (class "Default")
      (node (ref "J1A") (pin "33") (pinfunction "33_33") (pintype "passive"))
      (node (ref "MC1") (pin "49") (pinfunction "49_49") (pintype "passive"))
    )
    (net (code "87") (name "/MC1_B15_P16") (class "Default")
      (node (ref "J1A") (pin "35") (pinfunction "35_35") (pintype "passive"))
      (node (ref "MC1") (pin "50") (pinfunction "50_50") (pintype "passive"))
    )
    (net (code "88") (name "/MC1_B15_P17") (class "Default")
      (node (ref "J1A") (pin "37") (pinfunction "37_37") (pintype "passive"))
      (node (ref "MC1") (pin "55") (pinfunction "55_55") (pintype "passive"))
    )
    (net (code "89") (name "/MC1_B15_P18") (class "Default")
      (node (ref "J1A") (pin "39") (pinfunction "39_39") (pintype "passive"))
      (node (ref "MC1") (pin "56") (pinfunction "56_56") (pintype "passive"))
    )
    (net (code "90") (name "/MC1_B15_X0") (class "Default")
      (node (ref "J1B") (pin "16") (pinfunction "16_16") (pintype "passive"))
      (node (ref "J2") (pin "2") (pinfunction "Tfault_2") (pintype "output"))
      (node (ref "MC1") (pin "48") (pinfunction "48_48") (pintype "passive"))
    )
    (net (code "91") (name "/MC1_B15_X1") (class "Default")
      (node (ref "J1B") (pin "15") (pinfunction "15_15") (pintype "passive"))
      (node (ref "J2") (pin "3") (pinfunction "Tdis_3") (pintype "input"))
      (node (ref "MC1") (pin "47") (pinfunction "47_47") (pintype "passive"))
      (node (ref "R6") (pin "1") (pinfunction "1_1") (pintype "passive"))
    )
    (net (code "92") (name "/MC1_B15_X2") (class "Default")
      (node (ref "J1B") (pin "14") (pinfunction "14_14") (pintype "passive"))
      (node (ref "J2") (pin "4") (pinfunction "MOD_DEF(2)_4") (pintype "passive"))
      (node (ref "MC1") (pin "42") (pinfunction "42_42") (pintype "passive"))
      (node (ref "R1") (pin "1") (pinfunction "1_1") (pintype "passive"))
    )
    (net (code "93") (name "/MC1_B15_X3") (class "Default")
      (node (ref "J1B") (pin "13") (pinfunction "13_13") (pintype "passive"))
      (node (ref "J2") (pin "5") (pinfunction "MOD_DEF(1)_5") (pintype "passive"))
      (node (ref "MC1") (pin "41") (pinfunction "41_41") (pintype "passive"))
      (node (ref "R2") (pin "1") (pinfunction "1_1") (pintype "passive"))
    )
    (net (code "94") (name "/MC1_B15_X4") (class "Default")
      (node (ref "J1B") (pin "12") (pinfunction "12_12") (pintype "passive"))
      (node (ref "J2") (pin "6") (pinfunction "MOD_DEF(0)_6") (pintype "passive"))
      (node (ref "MC1") (pin "36") (pinfunction "36_36") (pintype "passive"))
      (node (ref "R3") (pin "1") (pinfunction "1_1") (pintype "passive"))
    )
    (net (code "95") (name "/MC1_B15_X5") (class "Default")
      (node (ref "J1B") (pin "11") (pinfunction "11_11") (pintype "passive"))
      (node (ref "J2") (pin "7") (pinfunction "Rate_Select_7") (pintype "input"))
      (node (ref "MC1") (pin "35") (pinfunction "35_35") (pintype "passive"))
      (node (ref "R4") (pin "1") (pinfunction "1_1") (pintype "passive"))
      (node (ref "R7") (pin "1") (pinfunction "1_1") (pintype "passive"))
    )
    (net (code "96") (name "/MC1_B15_X6") (class "Default")
      (node (ref "J1B") (pin "10") (pinfunction "10_10") (pintype "passive"))
      (node (ref "J2") (pin "8") (pinfunction "LOS_8") (pintype "output"))
      (node (ref "MC1") (pin "30") (pinfunction "30_30") (pintype "passive"))
      (node (ref "R5") (pin "1") (pinfunction "1_1") (pintype "passive"))
    )
    (net (code "97") (name "/MC1_B15_X7") (class "Default")
      (node (ref "J1B") (pin "9") (pinfunction "9_9") (pintype "passive"))
      (node (ref "MC1") (pin "29") (pinfunction "29_29") (pintype "passive"))
    )
    (net (code "98") (name "/MC1_B16_CLK_N") (class "Default")
      (node (ref "J1C") (pin "18") (pinfunction "18_18") (pintype "passive"))
      (node (ref "MC1") (pin "87") (pinfunction "87_87") (pintype "passive"))
    )
    (net (code "99") (name "/MC1_B16_CLK_P") (class "Default")
      (node (ref "J1C") (pin "17") (pinfunction "17_17") (pintype "passive"))
      (node (ref "MC1") (pin "85") (pinfunction "85_85") (pintype "passive"))
    )
    (net (code "100") (name "/MC1_B16_N0") (class "Default")
      (node (ref "J1C") (pin "2") (pinfunction "2_2") (pintype "passive"))
      (node (ref "MC1") (pin "63") (pinfunction "63_63") (pintype "passive"))
    )
    (net (code "101") (name "/MC1_B16_N1") (class "Default")
      (node (ref "J1C") (pin "4") (pinfunction "4_4") (pintype "passive"))
      (node (ref "MC1") (pin "64") (pinfunction "64_64") (pintype "passive"))
    )
    (net (code "102") (name "/MC1_B16_N2") (class "Default")
      (node (ref "J1C") (pin "6") (pinfunction "6_6") (pintype "passive"))
      (node (ref "MC1") (pin "69") (pinfunction "69_69") (pintype "passive"))
    )
    (net (code "103") (name "/MC1_B16_N3") (class "Default")
      (node (ref "J1C") (pin "8") (pinfunction "8_8") (pintype "passive"))
      (node (ref "MC1") (pin "70") (pinfunction "70_70") (pintype "passive"))
    )
    (net (code "104") (name "/MC1_B16_N4") (class "Default")
      (node (ref "J1C") (pin "10") (pinfunction "10_10") (pintype "passive"))
      (node (ref "MC1") (pin "75") (pinfunction "75_75") (pintype "passive"))
    )
    (net (code "105") (name "/MC1_B16_N5") (class "Default")
      (node (ref "J1C") (pin "12") (pinfunction "12_12") (pintype "passive"))
      (node (ref "MC1") (pin "76") (pinfunction "76_76") (pintype "passive"))
    )
    (net (code "106") (name "/MC1_B16_N6") (class "Default")
      (node (ref "J1C") (pin "14") (pinfunction "14_14") (pintype "passive"))
      (node (ref "MC1") (pin "81") (pinfunction "81_81") (pintype "passive"))
    )
    (net (code "107") (name "/MC1_B16_N7") (class "Default")
      (node (ref "J1C") (pin "16") (pinfunction "16_16") (pintype "passive"))
      (node (ref "MC1") (pin "82") (pinfunction "82_82") (pintype "passive"))
    )
    (net (code "108") (name "/MC1_B16_N8") (class "Default")
      (node (ref "J1C") (pin "20") (pinfunction "20_20") (pintype "passive"))
      (node (ref "MC1") (pin "88") (pinfunction "88_88") (pintype "passive"))
    )
    (net (code "109") (name "/MC1_B16_N9") (class "Default")
      (node (ref "J1C") (pin "22") (pinfunction "22_22") (pintype "passive"))
      (node (ref "MC1") (pin "93") (pinfunction "93_93") (pintype "passive"))
    )
    (net (code "110") (name "/MC1_B16_N10") (class "Default")
      (node (ref "J1C") (pin "24") (pinfunction "24_24") (pintype "passive"))
      (node (ref "MC1") (pin "94") (pinfunction "94_94") (pintype "passive"))
    )
    (net (code "111") (name "/MC1_B16_N11") (class "Default")
      (node (ref "J1C") (pin "26") (pinfunction "26_26") (pintype "passive"))
      (node (ref "MC1") (pin "99") (pinfunction "99_99") (pintype "passive"))
    )
    (net (code "112") (name "/MC1_B16_N12") (class "Default")
      (node (ref "J1C") (pin "28") (pinfunction "28_28") (pintype "passive"))
      (node (ref "MC1") (pin "100") (pinfunction "100_100") (pintype "passive"))
    )
    (net (code "113") (name "/MC1_B16_N13") (class "Default")
      (node (ref "J1C") (pin "30") (pinfunction "30_30") (pintype "passive"))
      (node (ref "MC1") (pin "105") (pinfunction "105_105") (pintype "passive"))
    )
    (net (code "114") (name "/MC1_B16_N14") (class "Default")
      (node (ref "J1C") (pin "32") (pinfunction "32_32") (pintype "passive"))
      (node (ref "MC1") (pin "106") (pinfunction "106_106") (pintype "passive"))
    )
    (net (code "115") (name "/MC1_B16_N15") (class "Default")
      (node (ref "J1C") (pin "34") (pinfunction "34_34") (pintype "passive"))
      (node (ref "MC1") (pin "111") (pinfunction "111_111") (pintype "passive"))
    )
    (net (code "116") (name "/MC1_B16_N16") (class "Default")
      (node (ref "J1C") (pin "36") (pinfunction "36_36") (pintype "passive"))
      (node (ref "MC1") (pin "112") (pinfunction "112_112") (pintype "passive"))
    )
    (net (code "117") (name "/MC1_B16_N17") (class "Default")
      (node (ref "J1C") (pin "38") (pinfunction "38_38") (pintype "passive"))
      (node (ref "MC1") (pin "117") (pinfunction "117_117") (pintype "passive"))
    )
    (net (code "118") (name "/MC1_B16_N18") (class "Default")
      (node (ref "J1C") (pin "40") (pinfunction "40_40") (pintype "passive"))
      (node (ref "MC1") (pin "118") (pinfunction "118_118") (pintype "passive"))
    )
    (net (code "119") (name "/MC1_B16_P0") (class "Default")
      (node (ref "J1C") (pin "1") (pinfunction "1_1") (pintype "passive"))
      (node (ref "MC1") (pin "61") (pinfunction "61_61") (pintype "passive"))
    )
    (net (code "120") (name "/MC1_B16_P1") (class "Default")
      (node (ref "J1C") (pin "3") (pinfunction "3_3") (pintype "passive"))
      (node (ref "MC1") (pin "62") (pinfunction "62_62") (pintype "passive"))
    )
    (net (code "121") (name "/MC1_B16_P2") (class "Default")
      (node (ref "J1C") (pin "5") (pinfunction "5_5") (pintype "passive"))
      (node (ref "MC1") (pin "67") (pinfunction "67_67") (pintype "passive"))
    )
    (net (code "122") (name "/MC1_B16_P3") (class "Default")
      (node (ref "J1C") (pin "7") (pinfunction "7_7") (pintype "passive"))
      (node (ref "MC1") (pin "68") (pinfunction "68_68") (pintype "passive"))
    )
    (net (code "123") (name "/MC1_B16_P4") (class "Default")
      (node (ref "J1C") (pin "9") (pinfunction "9_9") (pintype "passive"))
      (node (ref "MC1") (pin "73") (pinfunction "73_73") (pintype "passive"))
    )
    (net (code "124") (name "/MC1_B16_P5") (class "Default")
      (node (ref "J1C") (pin "11") (pinfunction "11_11") (pintype "passive"))
      (node (ref "MC1") (pin "74") (pinfunction "74_74") (pintype "passive"))
    )
    (net (code "125") (name "/MC1_B16_P6") (class "Default")
      (node (ref "J1C") (pin "13") (pinfunction "13_13") (pintype "passive"))
      (node (ref "MC1") (pin "79") (pinfunction "79_79") (pintype "passive"))
    )
    (net (code "126") (name "/MC1_B16_P7") (class "Default")
      (node (ref "J1C") (pin "15") (pinfunction "15_15") (pintype "passive"))
      (node (ref "MC1") (pin "80") (pinfunction "80_80") (pintype "passive"))
    )
    (net (code "127") (name "/MC1_B16_P8") (class "Default")
      (node (ref "J1C") (pin "19") (pinfunction "19_19") (pintype "passive"))
      (node (ref "MC1") (pin "86") (pinfunction "86_86") (pintype "passive"))
    )
    (net (code "128") (name "/MC1_B16_P9") (class "Default")
      (node (ref "J1C") (pin "21") (pinfunction "21_21") (pintype "passive"))
      (node (ref "MC1") (pin "91") (pinfunction "91_91") (pintype "passive"))
    )
    (net (code "129") (name "/MC1_B16_P10") (class "Default")
      (node (ref "J1C") (pin "23") (pinfunction "23_23") (pintype "passive"))
      (node (ref "MC1") (pin "92") (pinfunction "92_92") (pintype "passive"))
    )
    (net (code "130") (name "/MC1_B16_P11") (class "Default")
      (node (ref "J1C") (pin "25") (pinfunction "25_25") (pintype "passive"))
      (node (ref "MC1") (pin "97") (pinfunction "97_97") (pintype "passive"))
    )
    (net (code "131") (name "/MC1_B16_P12") (class "Default")
      (node (ref "J1C") (pin "27") (pinfunction "27_27") (pintype "passive"))
      (node (ref "MC1") (pin "98") (pinfunction "98_98") (pintype "passive"))
    )
    (net (code "132") (name "/MC1_B16_P13") (class "Default")
      (node (ref "J1C") (pin "29") (pinfunction "29_29") (pintype "passive"))
      (node (ref "MC1") (pin "103") (pinfunction "103_103") (pintype "passive"))
    )
    (net (code "133") (name "/MC1_B16_P14") (class "Default")
      (node (ref "J1C") (pin "31") (pinfunction "31_31") (pintype "passive"))
      (node (ref "MC1") (pin "104") (pinfunction "104_104") (pintype "passive"))
    )
    (net (code "134") (name "/MC1_B16_P15") (class "Default")
      (node (ref "J1C") (pin "33") (pinfunction "33_33") (pintype "passive"))
      (node (ref "MC1") (pin "109") (pinfunction "109_109") (pintype "passive"))
    )
    (net (code "135") (name "/MC1_B16_P16") (class "Default")
      (node (ref "J1C") (pin "35") (pinfunction "35_35") (pintype "passive"))
      (node (ref "MC1") (pin "110") (pinfunction "110_110") (pintype "passive"))
    )
    (net (code "136") (name "/MC1_B16_P17") (class "Default")
      (node (ref "J1C") (pin "37") (pinfunction "37_37") (pintype "passive"))
      (node (ref "MC1") (pin "115") (pinfunction "115_115") (pintype "passive"))
    )
    (net (code "137") (name "/MC1_B16_P18") (class "Default")
      (node (ref "J1C") (pin "39") (pinfunction "39_39") (pintype "passive"))
      (node (ref "MC1") (pin "116") (pinfunction "116_116") (pintype "passive"))
    )
    (net (code "138") (name "/MC1_B16_X0") (class "Default")
      (node (ref "J1D") (pin "16") (pinfunction "16_16") (pintype "passive"))
      (node (ref "J3") (pin "2") (pinfunction "Tfault_2") (pintype "output"))
      (node (ref "MC1") (pin "108") (pinfunction "108_108") (pintype "passive"))
    )
    (net (code "139") (name "/MC1_B16_X1") (class "Default")
      (node (ref "J1D") (pin "15") (pinfunction "15_15") (pintype "passive"))
      (node (ref "J3") (pin "3") (pinfunction "Tdis_3") (pintype "input"))
      (node (ref "MC1") (pin "107") (pinfunction "107_107") (pintype "passive"))
      (node (ref "R13") (pin "1") (pinfunction "1_1") (pintype "passive"))
    )
    (net (code "140") (name "/MC1_B16_X2") (class "Default")
      (node (ref "J1D") (pin "14") (pinfunction "14_14") (pintype "passive"))
      (node (ref "J3") (pin "4") (pinfunction "MOD_DEF(2)_4") (pintype "passive"))
      (node (ref "MC1") (pin "102") (pinfunction "102_102") (pintype "passive"))
      (node (ref "R8") (pin "2") (pinfunction "2_2") (pintype "passive"))
    )
    (net (code "141") (name "/MC1_B16_X3") (class "Default")
      (node (ref "J1D") (pin "13") (pinfunction "13_13") (pintype "passive"))
      (node (ref "J3") (pin "5") (pinfunction "MOD_DEF(1)_5") (pintype "passive"))
      (node (ref "MC1") (pin "101") (pinfunction "101_101") (pintype "passive"))
      (node (ref "R9") (pin "2") (pinfunction "2_2") (pintype "passive"))
    )
    (net (code "142") (name "/MC1_B16_X4") (class "Default")
      (node (ref "J1D") (pin "12") (pinfunction "12_12") (pintype "passive"))
      (node (ref "J3") (pin "6") (pinfunction "MOD_DEF(0)_6") (pintype "passive"))
      (node (ref "MC1") (pin "96") (pinfunction "96_96") (pintype "passive"))
      (node (ref "R10") (pin "2") (pinfunction "2_2") (pintype "passive"))
    )
    (net (code "143") (name "/MC1_B16_X5") (class "Default")
      (node (ref "J1D") (pin "11") (pinfunction "11_11") (pintype "passive"))
      (node (ref "J3") (pin "7") (pinfunction "Rate_Select_7") (pintype "input"))
      (node (ref "MC1") (pin "95") (pinfunction "95_95") (pintype "passive"))
      (node (ref "R11") (pin "2") (pinfunction "2_2") (pintype "passive"))
      (node (ref "R14") (pin "1") (pinfunction "1_1") (pintype "passive"))
    )
    (net (code "144") (name "/MC1_B16_X6") (class "Default")
      (node (ref "J1D") (pin "10") (pinfunction "10_10") (pintype "passive"))
      (node (ref "J3") (pin "8") (pinfunction "LOS_8") (pintype "output"))
      (node (ref "MC1") (pin "90") (pinfunction "90_90") (pintype "passive"))
      (node (ref "R12") (pin "2") (pinfunction "2_2") (pintype "passive"))
    )
    (net (code "145") (name "/MC1_B16_X7") (class "Default")
      (node (ref "J1D") (pin "9") (pinfunction "9_9") (pintype "passive"))
      (node (ref "MC1") (pin "89") (pinfunction "89_89") (pintype "passive"))
    )
    (net (code "146") (name "DGND") (class "Default")
      (node (ref "C1") (pin "1") (pinfunction "1_1") (pintype "passive"))
      (node (ref "J10") (pin "2") (pinfunction "GND_2") (pintype "passive"))
      (node (ref "J11") (pin "2") (pinfunction "GND_2") (pintype "passive"))
      (node (ref "J12") (pin "2") (pinfunction "GND_2") (pintype "passive"))
      (node (ref "J13") (pin "2") (pinfunction "GND_2") (pintype "passive"))
      (node (ref "J14") (pin "2") (pinfunction "GND_2") (pintype "passive"))
      (node (ref "J15") (pin "2") (pinfunction "GND_2") (pintype "passive"))
      (node (ref "J16") (pin "1") (pinfunction "GND_1") (pintype "passive"))
      (node (ref "J16") (pin "4") (pinfunction "GND_4") (pintype "passive"))
      (node (ref "J16") (pin "7") (pinfunction "GND_7") (pintype "passive"))
      (node (ref "J17") (pin "1") (pinfunction "GND_1") (pintype "passive"))
      (node (ref "J17") (pin "4") (pinfunction "GND_4") (pintype "passive"))
      (node (ref "J17") (pin "7") (pinfunction "GND_7") (pintype "passive"))
      (node (ref "J18") (pin "1") (pinfunction "GND_1") (pintype "passive"))
      (node (ref "J18") (pin "4") (pinfunction "GND_4") (pintype "passive"))
      (node (ref "J18") (pin "7") (pinfunction "GND_7") (pintype "passive"))
      (node (ref "J19") (pin "2") (pinfunction "GND_2") (pintype "passive"))
      (node (ref "J1B") (pin "1") (pinfunction "1_1") (pintype "passive"))
      (node (ref "J1B") (pin "17") (pinfunction "17_17") (pintype "passive"))
      (node (ref "J1B") (pin "18") (pinfunction "18_18") (pintype "passive"))
      (node (ref "J1B") (pin "2") (pinfunction "2_2") (pintype "passive"))
      (node (ref "J1B") (pin "3") (pinfunction "3_3") (pintype "passive"))
      (node (ref "J1B") (pin "4") (pinfunction "4_4") (pintype "passive"))
      (node (ref "J1B") (pin "5") (pinfunction "5_5") (pintype "passive"))
      (node (ref "J1B") (pin "6") (pinfunction "6_6") (pintype "passive"))
      (node (ref "J1B") (pin "7") (pinfunction "7_7") (pintype "passive"))
      (node (ref "J1B") (pin "8") (pinfunction "8_8") (pintype "passive"))
      (node (ref "J1D") (pin "1") (pinfunction "1_1") (pintype "passive"))
      (node (ref "J1D") (pin "17") (pinfunction "17_17") (pintype "passive"))
      (node (ref "J1D") (pin "2") (pinfunction "2_2") (pintype "passive"))
      (node (ref "J1D") (pin "3") (pinfunction "3_3") (pintype "passive"))
      (node (ref "J1D") (pin "4") (pinfunction "4_4") (pintype "passive"))
      (node (ref "J1D") (pin "5") (pinfunction "5_5") (pintype "passive"))
      (node (ref "J1D") (pin "6") (pinfunction "6_6") (pintype "passive"))
      (node (ref "J1D") (pin "7") (pinfunction "7_7") (pintype "passive"))
      (node (ref "J1D") (pin "8") (pinfunction "8_8") (pintype "passive"))
      (node (ref "J2") (pin "1") (pinfunction "Veet_1") (pintype "power_in"))
      (node (ref "J2") (pin "10") (pinfunction "Veer_10") (pintype "power_in"))
      (node (ref "J2") (pin "11") (pinfunction "Veer_11") (pintype "power_in"))
      (node (ref "J2") (pin "14") (pinfunction "Veer_14") (pintype "power_in"))
      (node (ref "J2") (pin "17") (pinfunction "Veet_17") (pintype "power_in"))
      (node (ref "J2") (pin "20") (pinfunction "Veet_20") (pintype "power_in"))
      (node (ref "J2") (pin "9") (pinfunction "Veer_9") (pintype "power_in"))
      (node (ref "J20") (pin "2") (pinfunction "GND_2") (pintype "passive"))
      (node (ref "J3") (pin "1") (pinfunction "Veet_1") (pintype "power_in"))
      (node (ref "J3") (pin "10") (pinfunction "Veer_10") (pintype "power_in"))
      (node (ref "J3") (pin "11") (pinfunction "Veer_11") (pintype "power_in"))
      (node (ref "J3") (pin "14") (pinfunction "Veer_14") (pintype "power_in"))
      (node (ref "J3") (pin "17") (pinfunction "Veet_17") (pintype "power_in"))
      (node (ref "J3") (pin "20") (pinfunction "Veet_20") (pintype "power_in"))
      (node (ref "J3") (pin "9") (pinfunction "Veer_9") (pintype "power_in"))
      (node (ref "J4") (pin "2") (pinfunction "GND_2") (pintype "passive"))
      (node (ref "J5") (pin "2") (pinfunction "GND_2") (pintype "passive"))
      (node (ref "J6") (pin "2") (pinfunction "GND_2") (pintype "passive"))
      (node (ref "J7") (pin "2") (pinfunction "GND_2") (pintype "passive"))
      (node (ref "J8") (pin "2") (pinfunction "GND_2") (pintype "passive"))
      (node (ref "J9") (pin "2") (pinfunction "GND_2") (pintype "passive"))
      (node (ref "MC1") (pin "0") (pinfunction "GND_0") (pintype "power_in"))
      (node (ref "MC1") (pin "11") (pinfunction "11_11") (pintype "passive"))
      (node (ref "MC1") (pin "113") (pinfunction "113_113") (pintype "passive"))
      (node (ref "MC1") (pin "12") (pinfunction "12_12") (pintype "passive"))
      (node (ref "MC1") (pin "125") (pinfunction "125_125") (pintype "passive"))
      (node (ref "MC1") (pin "126") (pinfunction "126_126") (pintype "passive"))
      (node (ref "MC1") (pin "131") (pinfunction "131_131") (pintype "passive"))
      (node (ref "MC1") (pin "132") (pinfunction "132_132") (pintype "passive"))
      (node (ref "MC1") (pin "137") (pinfunction "137_137") (pintype "passive"))
      (node (ref "MC1") (pin "138") (pinfunction "138_138") (pintype "passive"))
      (node (ref "MC1") (pin "143") (pinfunction "143_143") (pintype "passive"))
      (node (ref "MC1") (pin "144") (pinfunction "144_144") (pintype "passive"))
      (node (ref "MC1") (pin "149") (pinfunction "149_149") (pintype "passive"))
      (node (ref "MC1") (pin "150") (pinfunction "150_150") (pintype "passive"))
      (node (ref "MC1") (pin "155") (pinfunction "155_155") (pintype "passive"))
      (node (ref "MC1") (pin "156") (pinfunction "156_156") (pintype "passive"))
      (node (ref "MC1") (pin "161") (pinfunction "161_161") (pintype "passive"))
      (node (ref "MC1") (pin "162") (pinfunction "162_162") (pintype "passive"))
      (node (ref "MC1") (pin "167") (pinfunction "167_167") (pintype "passive"))
      (node (ref "MC1") (pin "168") (pinfunction "168_168") (pintype "passive"))
      (node (ref "MC1") (pin "17") (pinfunction "17_17") (pintype "passive"))
      (node (ref "MC1") (pin "173") (pinfunction "173_173") (pintype "passive"))
      (node (ref "MC1") (pin "174") (pinfunction "174_174") (pintype "passive"))
      (node (ref "MC1") (pin "175") (pinfunction "175_175") (pintype "passive"))
      (node (ref "MC1") (pin "176") (pinfunction "176_176") (pintype "passive"))
      (node (ref "MC1") (pin "177") (pinfunction "177_177") (pintype "passive"))
      (node (ref "MC1") (pin "178") (pinfunction "178_178") (pintype "passive"))
      (node (ref "MC1") (pin "179") (pinfunction "179_179") (pintype "passive"))
      (node (ref "MC1") (pin "18") (pinfunction "18_18") (pintype "passive"))
      (node (ref "MC1") (pin "180") (pinfunction "180_180") (pintype "passive"))
      (node (ref "MC1") (pin "23") (pinfunction "23_23") (pintype "passive"))
      (node (ref "MC1") (pin "24") (pinfunction "24_24") (pintype "passive"))
      (node (ref "MC1") (pin "5") (pinfunction "5_5") (pintype "passive"))
      (node (ref "MC1") (pin "53") (pinfunction "53_53") (pintype "passive"))
      (node (ref "MC1") (pin "54") (pinfunction "54_54") (pintype "passive"))
      (node (ref "MC1") (pin "6") (pinfunction "6_6") (pintype "passive"))
      (node (ref "MC1") (pin "65") (pinfunction "65_65") (pintype "passive"))
      (node (ref "MC1") (pin "66") (pinfunction "66_66") (pintype "passive"))
      (node (ref "MC1") (pin "71") (pinfunction "71_71") (pintype "passive"))
      (node (ref "MC1") (pin "72") (pinfunction "72_72") (pintype "passive"))
      (node (ref "MC1") (pin "77") (pinfunction "77_77") (pintype "passive"))
      (node (ref "MC1") (pin "78") (pinfunction "78_78") (pintype "passive"))
      (node (ref "MC1") (pin "83") (pinfunction "83_83") (pintype "passive"))
      (node (ref "MC1") (pin "84") (pinfunction "84_84") (pintype "passive"))
      (node (ref "R13") (pin "2") (pinfunction "2_2") (pintype "passive"))
      (node (ref "R14") (pin "2") (pinfunction "2_2") (pintype "passive"))
      (node (ref "R6") (pin "2") (pinfunction "2_2") (pintype "passive"))
      (node (ref "R7") (pin "2") (pinfunction "2_2") (pintype "passive"))
      (node (ref "U3") (pin "3") (pinfunction "GND_3") (pintype "power_in"))
    )
    (net (code "147") (name "MC1_VREF1") (class "Default")
      (node (ref "J1D") (pin "18") (pinfunction "18_18") (pintype "passive"))
      (node (ref "MC1") (pin "114") (pinfunction "114_114") (pintype "passive"))
    )
    (net (code "148") (name "Net-(J4-SIGNAL)") (class "Default")
      (node (ref "C20") (pin "1") (pinfunction "1_1") (pintype "passive"))
      (node (ref "J4") (pin "1") (pinfunction "SIGNAL_1") (pintype "passive"))
    )
    (net (code "149") (name "Net-(J5-SIGNAL)") (class "Default")
      (node (ref "C21") (pin "1") (pinfunction "1_1") (pintype "passive"))
      (node (ref "J5") (pin "1") (pinfunction "SIGNAL_1") (pintype "passive"))
    )
    (net (code "150") (name "Net-(J6-SIGNAL)") (class "Default")
      (node (ref "C22") (pin "1") (pinfunction "1_1") (pintype "passive"))
      (node (ref "J6") (pin "1") (pinfunction "SIGNAL_1") (pintype "passive"))
    )
    (net (code "151") (name "Net-(J7-SIGNAL)") (class "Default")
      (node (ref "C23") (pin "1") (pinfunction "1_1") (pintype "passive"))
      (node (ref "J7") (pin "1") (pinfunction "SIGNAL_1") (pintype "passive"))
    )
    (net (code "152") (name "Net-(J8-SIGNAL)") (class "Default")
      (node (ref "C24") (pin "1") (pinfunction "1_1") (pintype "passive"))
      (node (ref "J8") (pin "1") (pinfunction "SIGNAL_1") (pintype "passive"))
    )
    (net (code "153") (name "Net-(J9-SIGNAL)") (class "Default")
      (node (ref "C25") (pin "1") (pinfunction "1_1") (pintype "passive"))
      (node (ref "J9") (pin "1") (pinfunction "SIGNAL_1") (pintype "passive"))
    )
    (net (code "154") (name "Net-(J10-SIGNAL)") (class "Default")
      (node (ref "C26") (pin "1") (pinfunction "1_1") (pintype "passive"))
      (node (ref "J10") (pin "1") (pinfunction "SIGNAL_1") (pintype "passive"))
    )
    (net (code "155") (name "Net-(J11-SIGNAL)") (class "Default")
      (node (ref "C27") (pin "1") (pinfunction "1_1") (pintype "passive"))
      (node (ref "J11") (pin "1") (pinfunction "SIGNAL_1") (pintype "passive"))
    )
    (net (code "156") (name "Net-(J12-SIGNAL)") (class "Default")
      (node (ref "C28") (pin "1") (pinfunction "1_1") (pintype "passive"))
      (node (ref "J12") (pin "1") (pinfunction "SIGNAL_1") (pintype "passive"))
    )
    (net (code "157") (name "Net-(J13-SIGNAL)") (class "Default")
      (node (ref "C29") (pin "1") (pinfunction "1_1") (pintype "passive"))
      (node (ref "J13") (pin "1") (pinfunction "SIGNAL_1") (pintype "passive"))
    )
    (net (code "158") (name "Net-(J14-SIGNAL)") (class "Default")
      (node (ref "C30") (pin "1") (pinfunction "1_1") (pintype "passive"))
      (node (ref "J14") (pin "1") (pinfunction "SIGNAL_1") (pintype "passive"))
    )
    (net (code "159") (name "Net-(J15-SIGNAL)") (class "Default")
      (node (ref "C31") (pin "1") (pinfunction "1_1") (pintype "passive"))
      (node (ref "J15") (pin "1") (pinfunction "SIGNAL_1") (pintype "passive"))
    )
    (net (code "160") (name "VADJ1") (class "Default")
      (node (ref "J1B") (pin "19") (pinfunction "19_19") (pintype "passive"))
      (node (ref "J1B") (pin "20") (pinfunction "20_20") (pintype "passive"))
      (node (ref "J1D") (pin "19") (pinfunction "19_19") (pintype "passive"))
      (node (ref "J1D") (pin "20") (pinfunction "20_20") (pintype "passive"))
      (node (ref "MC1") (pin "119") (pinfunction "119_119") (pintype "passive"))
      (node (ref "MC1") (pin "120") (pinfunction "120_120") (pintype "passive"))
      (node (ref "MC1") (pin "59") (pinfunction "59_59") (pintype "passive"))
      (node (ref "MC1") (pin "60") (pinfunction "60_60") (pintype "passive"))
      (node (ref "TP1") (pin "1") (pinfunction "PIN_1") (pintype "passive"))
    )
    (net (code "161") (name "unconnected-(J16-MH-PadMH1)") (class "Default")
      (node (ref "J16") (pin "MH1") (pinfunction "MH_MH1") (pintype "passive+no_connect"))
    )
    (net (code "162") (name "unconnected-(J16-MH-PadMH2)") (class "Default")
      (node (ref "J16") (pin "MH2") (pinfunction "MH_MH2") (pintype "passive+no_connect"))
    )
    (net (code "163") (name "unconnected-(J17-MH-PadMH1)") (class "Default")
      (node (ref "J17") (pin "MH1") (pinfunction "MH_MH1") (pintype "passive+no_connect"))
    )
    (net (code "164") (name "unconnected-(J17-MH-PadMH2)") (class "Default")
      (node (ref "J17") (pin "MH2") (pinfunction "MH_MH2") (pintype "passive+no_connect"))
    )
    (net (code "165") (name "unconnected-(J18-MH-PadMH1)") (class "Default")
      (node (ref "J18") (pin "MH1") (pinfunction "MH_MH1") (pintype "passive+no_connect"))
    )
    (net (code "166") (name "unconnected-(J18-MH-PadMH2)") (class "Default")
      (node (ref "J18") (pin "MH2") (pinfunction "MH_MH2") (pintype "passive+no_connect"))
    )
  )
)
